# Sheet1.net
KiCad netlist of a schematic drawn in Altium Designer
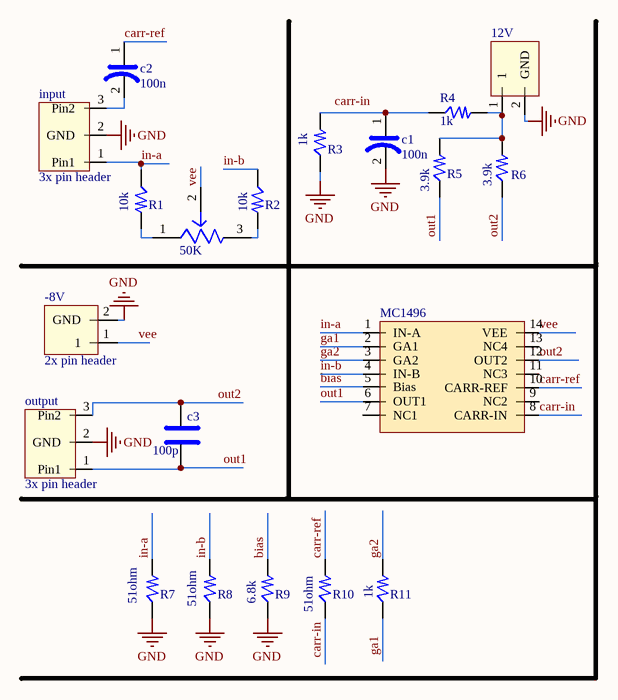
[diagram p0: Sheet1.SchDoc]

(export (version "E")
  (design (tool "Eeschema 10.0.6"))
  (components
    (comp (ref "-8V")
      (value "2x pin header")
      (footprint "2x pin header")
      (libsource (lib "Schlib1") (part "2x pin header"))
    )
    (comp (ref "12V")
      (value "2x pin header")
      (footprint "2x pin header")
      (libsource (lib "") (part "2x pin header_1"))
    )
    (comp (ref "50K")
      (value "3296 potenciometer")
      (footprint "3296 potenciometer")
      (libsource (lib "Schlib1") (part "3296 potenciometer"))
    )
    (comp (ref "c1")
      (value "100n")
      (footprint "100n cap")
      (libsource (lib "Schlib1") (part "100n capacitor"))
    )
    (comp (ref "c2")
      (value "100n")
      (footprint "100n cap")
      (libsource (lib "Schlib1") (part "100n capacitor"))
    )
    (comp (ref "c3")
      (value "100p")
      (footprint "100p capacitor")
      (libsource (lib "Schlib1") (part "100p capacitor"))
    )
    (comp (ref "input")
      (value "3x pin header")
      (footprint "3x pin header")
      (libsource (lib "Schlib1") (part "3x pin header"))
    )
    (comp (ref "MC1496")
      (value "MC1496.PP")
      (footprint "DIP-14-7.62mm")
      (libsource (lib "Schlib1") (part "MC1496.Dipp"))
    )
    (comp (ref "output")
      (value "3x pin header")
      (footprint "3x pin header")
      (libsource (lib "Schlib1") (part "3x pin header"))
    )
    (comp (ref "R1")
      (value "10k")
      (footprint "R_AXIAL_0.25W")
      (libsource (lib "Schlib1") (part "RESISTOR_Dipp"))
    )
    (comp (ref "R2")
      (value "10k")
      (footprint "R_AXIAL_0.25W")
      (libsource (lib "Schlib1") (part "RESISTOR_Dipp"))
    )
    (comp (ref "R3")
      (value "1k")
      (footprint "R_AXIAL_0.25W")
      (libsource (lib "Schlib1") (part "RESISTOR_Dipp"))
    )
    (comp (ref "R4")
      (value "1k")
      (footprint "R_AXIAL_0.25W")
      (libsource (lib "Schlib1") (part "RESISTOR_Dipp"))
    )
    (comp (ref "R5")
      (value "3.9k")
      (footprint "R_AXIAL_0.25W")
      (libsource (lib "Schlib1") (part "RESISTOR_Dipp"))
    )
    (comp (ref "R6")
      (value "3.9k")
      (footprint "R_AXIAL_0.25W")
      (libsource (lib "Schlib1") (part "RESISTOR_Dipp"))
    )
    (comp (ref "R7")
      (value "51ohm")
      (footprint "R_AXIAL_0.25W")
      (libsource (lib "Schlib1") (part "RESISTOR_Dipp"))
    )
    (comp (ref "R8")
      (value "51ohm")
      (footprint "R_AXIAL_0.25W")
      (libsource (lib "Schlib1") (part "RESISTOR_Dipp"))
    )
    (comp (ref "R9")
      (value "6.8k")
      (footprint "R_AXIAL_0.25W")
      (libsource (lib "Schlib1") (part "RESISTOR_Dipp"))
    )
    (comp (ref "R10")
      (value "51ohm")
      (footprint "R_AXIAL_0.25W")
      (libsource (lib "Schlib1") (part "RESISTOR_Dipp"))
    )
    (comp (ref "R11")
      (value "1k")
      (footprint "R_AXIAL_0.25W")
      (libsource (lib "Schlib1") (part "RESISTOR_Dipp"))
    )
  )
  (nets
    (net (code "1") (name "/bias") (class "Default")
      (node (ref "MC1496") (pin "5") (pinfunction "Bias_5") (pintype "passive"))
      (node (ref "R9") (pin "2") (pinfunction "2_2") (pintype "passive"))
    )
    (net (code "2") (name "/carr-in") (class "Default")
      (node (ref "MC1496") (pin "8") (pinfunction "CARR-IN_8") (pintype "passive"))
      (node (ref "R10") (pin "1") (pinfunction "1_1") (pintype "passive"))
    )
    (net (code "3") (name "/carr-ref") (class "Default")
      (node (ref "MC1496") (pin "10") (pinfunction "CARR-REF_10") (pintype "passive"))
      (node (ref "R10") (pin "2") (pinfunction "2_2") (pintype "passive"))
      (node (ref "c2") (pin "1") (pinfunction "1_1") (pintype "passive"))
    )
    (net (code "4") (name "/ga1") (class "Default")
      (node (ref "MC1496") (pin "2") (pinfunction "GA1_2") (pintype "passive"))
      (node (ref "R11") (pin "1") (pinfunction "1_1") (pintype "passive"))
    )
    (net (code "5") (name "/ga2") (class "Default")
      (node (ref "MC1496") (pin "3") (pinfunction "GA2_3") (pintype "passive"))
      (node (ref "R11") (pin "2") (pinfunction "2_2") (pintype "passive"))
    )
    (net (code "6") (name "/in-a") (class "Default")
      (node (ref "MC1496") (pin "1") (pinfunction "IN-A_1") (pintype "passive"))
      (node (ref "R1") (pin "1") (pinfunction "1_1") (pintype "passive"))
      (node (ref "R7") (pin "2") (pinfunction "2_2") (pintype "passive"))
      (node (ref "input") (pin "1") (pinfunction "Pin1_1") (pintype "passive"))
    )
    (net (code "7") (name "/in-b") (class "Default")
      (node (ref "MC1496") (pin "4") (pinfunction "IN-B_4") (pintype "passive"))
      (node (ref "R2") (pin "1") (pinfunction "1_1") (pintype "passive"))
      (node (ref "R8") (pin "2") (pinfunction "2_2") (pintype "passive"))
    )
    (net (code "8") (name "/out1") (class "Default")
      (node (ref "MC1496") (pin "6") (pinfunction "OUT1_6") (pintype "passive"))
      (node (ref "R5") (pin "1") (pinfunction "1_1") (pintype "passive"))
      (node (ref "c3") (pin "2") (pinfunction "2_2") (pintype "passive"))
      (node (ref "output") (pin "1") (pinfunction "Pin1_1") (pintype "passive"))
    )
    (net (code "9") (name "/out2") (class "Default")
      (node (ref "MC1496") (pin "12") (pinfunction "OUT2_12") (pintype "passive"))
      (node (ref "R6") (pin "1") (pinfunction "1_1") (pintype "passive"))
      (node (ref "c3") (pin "1") (pinfunction "1_1") (pintype "passive"))
      (node (ref "output") (pin "3") (pinfunction "Pin2_3") (pintype "passive"))
    )
    (net (code "10") (name "/vee") (class "Default")
      (node (ref "-8V") (pin "1") (pinfunction "1_1") (pintype "passive"))
      (node (ref "50K") (pin "2") (pinfunction "2_2") (pintype "passive"))
      (node (ref "MC1496") (pin "14") (pinfunction "VEE_14") (pintype "passive"))
    )
    (net (code "11") (name "GND") (class "Default")
      (node (ref "-8V") (pin "2") (pinfunction "GND_2") (pintype "passive"))
      (node (ref "12V") (pin "2") (pinfunction "GND_2") (pintype "passive"))
      (node (ref "R3") (pin "1") (pinfunction "1_1") (pintype "passive"))
      (node (ref "R7") (pin "1") (pinfunction "1_1") (pintype "passive"))
      (node (ref "R8") (pin "1") (pinfunction "1_1") (pintype "passive"))
      (node (ref "R9") (pin "1") (pinfunction "1_1") (pintype "passive"))
      (node (ref "c1") (pin "2") (pinfunction "2_2") (pintype "passive"))
      (node (ref "input") (pin "2") (pinfunction "GND_2") (pintype "passive"))
      (node (ref "output") (pin "2") (pinfunction "GND_2") (pintype "passive"))
    )
    (net (code "12") (name "Net-(12V-Pad1)") (class "Default")
      (node (ref "12V") (pin "1") (pinfunction "1_1") (pintype "passive"))
      (node (ref "R4") (pin "2") (pinfunction "2_2") (pintype "passive"))
      (node (ref "R5") (pin "2") (pinfunction "2_2") (pintype "passive"))
      (node (ref "R6") (pin "2") (pinfunction "2_2") (pintype "passive"))
    )
    (net (code "13") (name "Net-(50K-Pad1)") (class "Default")
      (node (ref "50K") (pin "1") (pinfunction "1_1") (pintype "passive"))
      (node (ref "R1") (pin "2") (pinfunction "2_2") (pintype "passive"))
    )
    (net (code "14") (name "Net-(50K-Pad3)") (class "Default")
      (node (ref "50K") (pin "3") (pinfunction "3_3") (pintype "passive"))
      (node (ref "R2") (pin "2") (pinfunction "2_2") (pintype "passive"))
    )
    (net (code "15") (name "Net-(R3-Pad2)") (class "Default")
      (node (ref "R3") (pin "2") (pinfunction "2_2") (pintype "passive"))
      (node (ref "R4") (pin "1") (pinfunction "1_1") (pintype "passive"))
      (node (ref "c1") (pin "1") (pinfunction "1_1") (pintype "passive"))
    )
    (net (code "16") (name "Net-(input-Pin2)") (class "Default")
      (node (ref "c2") (pin "2") (pinfunction "2_2") (pintype "passive"))
      (node (ref "input") (pin "3") (pinfunction "Pin2_3") (pintype "passive"))
    )
    (net (code "17") (name "unconnected-(MC1496-NC1-Pad7)") (class "Default")
      (node (ref "MC1496") (pin "7") (pinfunction "NC1_7") (pintype "passive"))
    )
    (net (code "18") (name "unconnected-(MC1496-NC2-Pad9)") (class "Default")
      (node (ref "MC1496") (pin "9") (pinfunction "NC2_9") (pintype "passive"))
    )
    (net (code "19") (name "unconnected-(MC1496-NC3-Pad11)") (class "Default")
      (node (ref "MC1496") (pin "11") (pinfunction "NC3_11") (pintype "passive"))
    )
    (net (code "20") (name "unconnected-(MC1496-NC4-Pad13)") (class "Default")
      (node (ref "MC1496") (pin "13") (pinfunction "NC4_13") (pintype "passive"))
    )
  )
)
